# main.net
KiCad netlist of a schematic drawn in Altium Designer
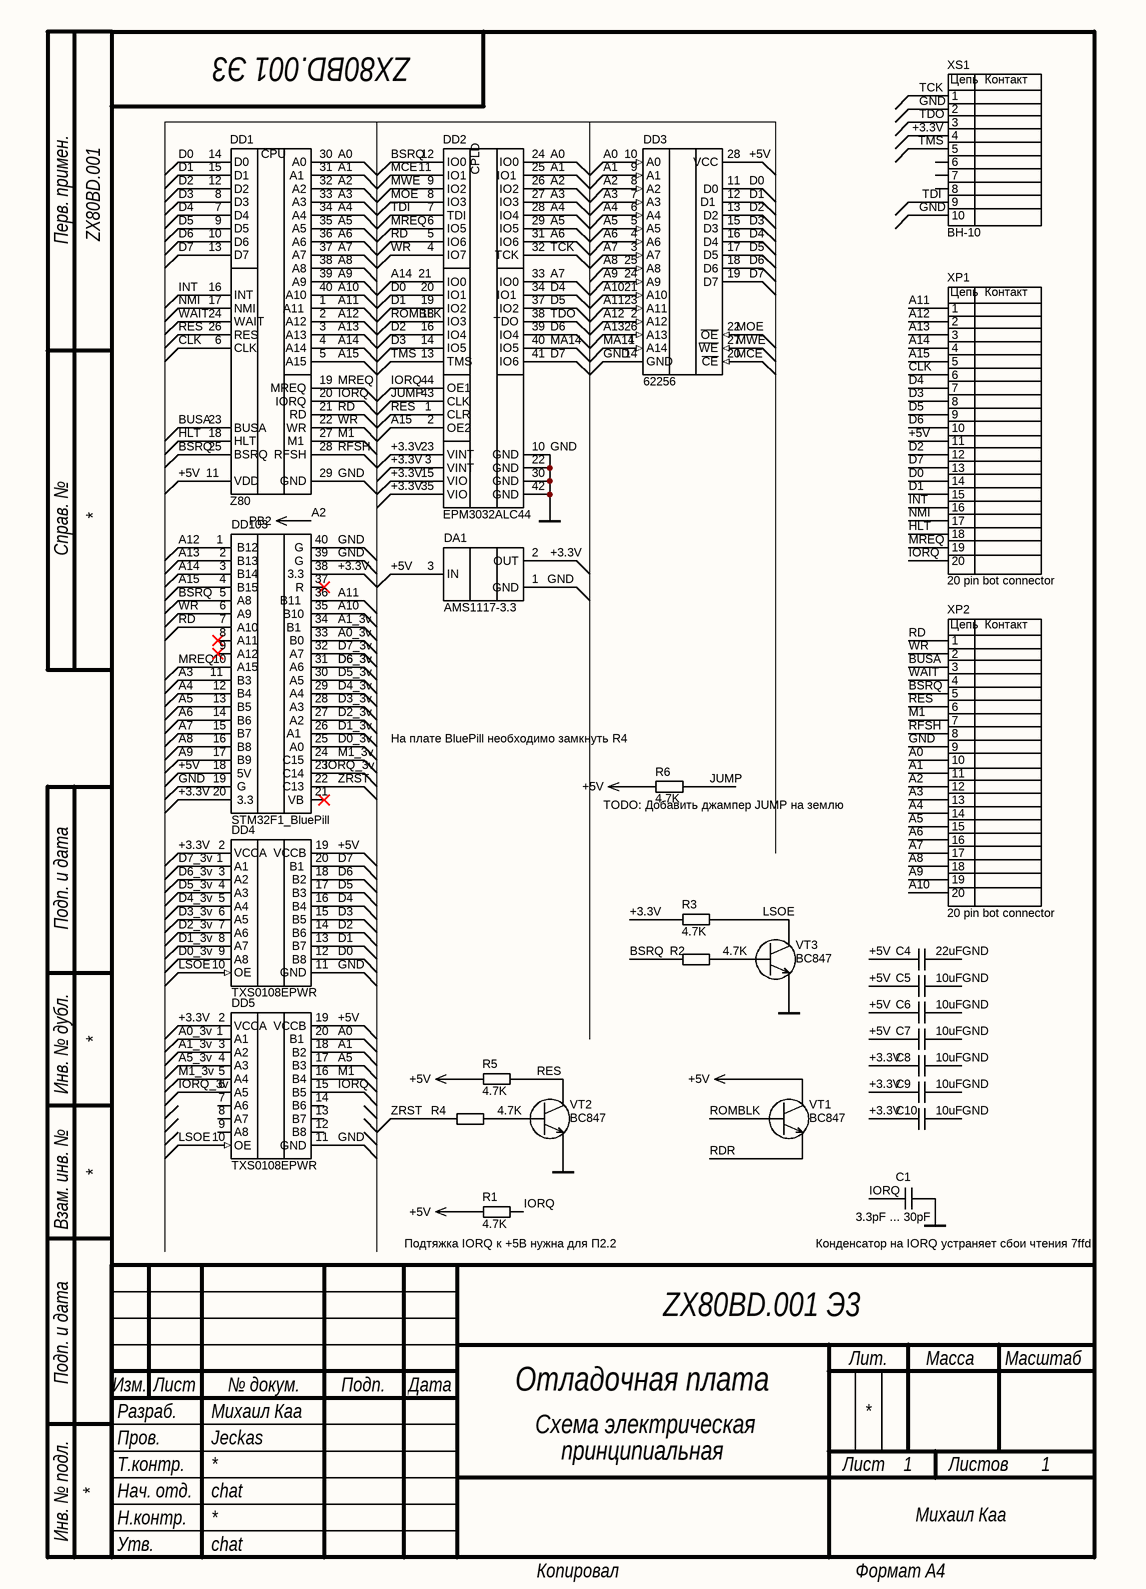
[diagram p0: main.SchDoc]

(export (version "E")
  (design (tool "Eeschema 10.0.6"))
  (components
    (comp (ref "C1")
      (value "3.3pF ... 30pF")
      (footprint "C0805")
      (libsource (lib "Capacitors") (part "CapCer"))
    )
    (comp (ref "C4") (value "22uF") (footprint "С1206") (libsource (lib "Capacitors") (part "CapCer")))
    (comp (ref "C5") (value "10uF") (footprint "C0805") (libsource (lib "Capacitors") (part "CapCer")))
    (comp (ref "C6") (value "10uF") (footprint "C0805") (libsource (lib "Capacitors") (part "CapCer")))
    (comp (ref "C7") (value "10uF") (footprint "C0805") (libsource (lib "Capacitors") (part "CapCer")))
    (comp (ref "C8") (value "10uF") (footprint "C0805") (libsource (lib "Capacitors") (part "CapCer")))
    (comp (ref "C9") (value "10uF") (footprint "C0805") (libsource (lib "Capacitors") (part "CapCer")))
    (comp (ref "C10") (value "10uF") (footprint "C0805") (libsource (lib "Capacitors") (part "CapCer")))
    (comp (ref "DA1")
      (value "AMS1117-3.3")
      (footprint "SOT229P700X180-4N")
      (libsource (lib "LDO") (part "AMS1117-3.3"))
    )
    (comp (ref "DD1")
      (value "Z80")
      (footprint "DIP1540W47P254L5320H635Q40B")
      (libsource (lib "Z80") (part "Z80"))
    )
    (comp (ref "DD2")
      (value "EPM3032ALC44")
      (footprint "PLCC-44-R")
      (description "44-Pin PLCC44")
      (libsource (lib "cpld") (part "EPM3032ALC44"))
    )
    (comp (ref "DD3")
      (value "62256")
      (footprint "DIP28")
      (fields (field (name "MF") "BRADY"))
      (libsource (lib "RAM") (part "62256"))
    )
    (comp (ref "DD4")
      (value "TXS0108EPWR")
      (footprint "SOP65P640X120-20N")
      (description "8-bit bidirectional voltage-level shifter for open-drain and push-pull application")
      (fields (field (name "MF") "Texas Instruments"))
      (libsource (lib "Shifter") (part "TXS0108EPWR"))
    )
    (comp (ref "DD5")
      (value "TXS0108EPWR")
      (footprint "SOP65P640X120-20N")
      (description "8-bit bidirectional voltage-level shifter for open-drain and push-pull application")
      (fields (field (name "MF") "Texas Instruments"))
      (libsource (lib "Shifter") (part "TXS0108EPWR"))
    )
    (comp (ref "DD103")
      (value "STM32F1_BluePill")
      (footprint "PCB-STM32F103")
      (description "STM32F103C8T6")
      (libsource (lib "MCU") (part "STM32F1_BluePill"))
    )
    (comp (ref "R1") (value "4.7K") (footprint "R0805") (libsource (lib "Resistors") (part "Res")))
    (comp (ref "R2") (value "4.7K") (footprint "R0805") (libsource (lib "Resistors") (part "Res")))
    (comp (ref "R3") (value "4.7K") (footprint "R0805") (libsource (lib "Resistors") (part "Res")))
    (comp (ref "R4") (value "4.7K") (footprint "R0805") (libsource (lib "Resistors") (part "Res")))
    (comp (ref "R5") (value "4.7K") (footprint "R0805") (libsource (lib "Resistors") (part "Res")))
    (comp (ref "R6") (value "4.7K") (footprint "R0805") (libsource (lib "Resistors") (part "Res")))
    (comp (ref "VT1")
      (value "BC847")
      (footprint "BC847")
      (description "NPN Transistor")
      (libsource (lib "Transistors") (part "BC847"))
    )
    (comp (ref "VT2")
      (value "BC847")
      (footprint "BC847")
      (description "NPN Transistor")
      (libsource (lib "Transistors") (part "BC847"))
    )
    (comp (ref "VT3")
      (value "BC847")
      (footprint "BC847")
      (description "NPN Transistor")
      (libsource (lib "Transistors") (part "BC847"))
    )
    (comp (ref "XP1")
      (value "20 pin bot connector")
      (footprint "20pin header")
      (description "20 Pin 2.54 mm")
      (libsource (lib "Connectors") (part "20 pin bot connector"))
    )
    (comp (ref "XP2")
      (value "20 pin bot connector")
      (footprint "20pin header")
      (description "20 Pin 2.54 mm")
      (libsource (lib "Connectors") (part "20 pin bot connector"))
    )
    (comp (ref "XS1")
      (value "BH-10")
      (footprint "BH-10")
      (description "10 Position Total Dual Row 2.54 mm Pitch Straight Male Shrouded Box Header")
      (fields (field (name "MF") "Sullins Connector") (field (name "MP") "SBH11-PBPC-D05-ST-BK"))
      (libsource (lib "Connectors") (part "BH-10"))
    )
  )
  (nets
    (net (code "1") (name "+5V") (class "Default")
      (node (ref "C4") (pin "1") (pinfunction "1_1") (pintype "passive"))
      (node (ref "C5") (pin "1") (pinfunction "1_1") (pintype "passive"))
      (node (ref "C6") (pin "1") (pinfunction "1_1") (pintype "passive"))
      (node (ref "C7") (pin "1") (pinfunction "1_1") (pintype "passive"))
      (node (ref "DA1") (pin "3") (pinfunction "IN_3") (pintype "passive"))
      (node (ref "DD1") (pin "11") (pinfunction "VDD_11") (pintype "passive"))
      (node (ref "DD103") (pin "18") (pinfunction "5V_18") (pintype "passive"))
      (node (ref "DD3") (pin "28") (pinfunction "VCC_28") (pintype "power_in"))
      (node (ref "DD4") (pin "19") (pinfunction "VCCB_19") (pintype "power_in"))
      (node (ref "DD5") (pin "19") (pinfunction "VCCB_19") (pintype "power_in"))
      (node (ref "R1") (pin "2") (pinfunction "2_2") (pintype "passive"))
      (node (ref "R5") (pin "2") (pinfunction "2_2") (pintype "passive"))
      (node (ref "R6") (pin "2") (pinfunction "2_2") (pintype "passive"))
      (node (ref "VT1") (pin "3") (pinfunction "C_3") (pintype "power_in"))
      (node (ref "XP1") (pin "11") (pinfunction "11_11") (pintype "passive"))
    )
    (net (code "2") (name "/+3.3V") (class "Default")
      (node (ref "C10") (pin "1") (pinfunction "1_1") (pintype "passive"))
      (node (ref "C8") (pin "1") (pinfunction "1_1") (pintype "passive"))
      (node (ref "C9") (pin "1") (pinfunction "1_1") (pintype "passive"))
      (node (ref "DA1") (pin "2") (pinfunction "OUT_2") (pintype "passive"))
      (node (ref "DD103") (pin "20") (pinfunction "3.3_20") (pintype "passive"))
      (node (ref "DD103") (pin "38") (pinfunction "3.3_38") (pintype "passive"))
      (node (ref "DD2") (pin "15") (pinfunction "VIO_15") (pintype "passive"))
      (node (ref "DD2") (pin "23") (pinfunction "VINT_23") (pintype "passive"))
      (node (ref "DD2") (pin "3") (pinfunction "VINT_3") (pintype "passive"))
      (node (ref "DD2") (pin "35") (pinfunction "VIO_35") (pintype "passive"))
      (node (ref "DD4") (pin "2") (pinfunction "VCCA_2") (pintype "power_in"))
      (node (ref "DD5") (pin "2") (pinfunction "VCCA_2") (pintype "power_in"))
      (node (ref "R3") (pin "2") (pinfunction "2_2") (pintype "passive"))
      (node (ref "XS1") (pin "4") (pinfunction "4_4") (pintype "passive"))
    )
    (net (code "3") (name "/A0") (class "Default")
      (node (ref "DD1") (pin "30") (pinfunction "A0_30") (pintype "passive"))
      (node (ref "DD2") (pin "24") (pinfunction "IO0_24") (pintype "passive"))
      (node (ref "DD3") (pin "10") (pinfunction "A0_10") (pintype "input"))
      (node (ref "DD5") (pin "20") (pinfunction "B1_20") (pintype "bidirectional"))
      (node (ref "XP2") (pin "10") (pinfunction "10_10") (pintype "passive"))
    )
    (net (code "4") (name "/A0_3v") (class "Default")
      (node (ref "DD103") (pin "33") (pinfunction "B0_33") (pintype "passive"))
      (node (ref "DD5") (pin "1") (pinfunction "A1_1") (pintype "bidirectional"))
    )
    (net (code "5") (name "/A1") (class "Default")
      (node (ref "DD1") (pin "31") (pinfunction "A1_31") (pintype "passive"))
      (node (ref "DD2") (pin "25") (pinfunction "IO1_25") (pintype "passive"))
      (node (ref "DD3") (pin "9") (pinfunction "A1_9") (pintype "input"))
      (node (ref "DD5") (pin "18") (pinfunction "B2_18") (pintype "bidirectional"))
      (node (ref "XP2") (pin "11") (pinfunction "11_11") (pintype "passive"))
    )
    (net (code "6") (name "/A1_3v") (class "Default")
      (node (ref "DD103") (pin "34") (pinfunction "B1_34") (pintype "passive"))
      (node (ref "DD5") (pin "3") (pinfunction "A2_3") (pintype "bidirectional"))
    )
    (net (code "7") (name "/A3") (class "Default")
      (node (ref "DD1") (pin "33") (pinfunction "A3_33") (pintype "passive"))
      (node (ref "DD103") (pin "11") (pinfunction "B3_11") (pintype "passive"))
      (node (ref "DD2") (pin "27") (pinfunction "IO3_27") (pintype "passive"))
      (node (ref "DD3") (pin "7") (pinfunction "A3_7") (pintype "input"))
      (node (ref "XP2") (pin "13") (pinfunction "13_13") (pintype "passive"))
    )
    (net (code "8") (name "/A4") (class "Default")
      (node (ref "DD1") (pin "34") (pinfunction "A4_34") (pintype "passive"))
      (node (ref "DD103") (pin "12") (pinfunction "B4_12") (pintype "passive"))
      (node (ref "DD2") (pin "28") (pinfunction "IO4_28") (pintype "passive"))
      (node (ref "DD3") (pin "6") (pinfunction "A4_6") (pintype "input"))
      (node (ref "XP2") (pin "14") (pinfunction "14_14") (pintype "passive"))
    )
    (net (code "9") (name "/A5") (class "Default")
      (node (ref "DD1") (pin "35") (pinfunction "A5_35") (pintype "passive"))
      (node (ref "DD103") (pin "13") (pinfunction "B5_13") (pintype "passive"))
      (node (ref "DD2") (pin "29") (pinfunction "IO5_29") (pintype "passive"))
      (node (ref "DD3") (pin "5") (pinfunction "A5_5") (pintype "input"))
      (node (ref "DD5") (pin "17") (pinfunction "B3_17") (pintype "bidirectional"))
      (node (ref "XP2") (pin "15") (pinfunction "15_15") (pintype "passive"))
    )
    (net (code "10") (name "/A5_3v") (class "Default")
      (node (ref "DD5") (pin "4") (pinfunction "A3_4") (pintype "bidirectional"))
    )
    (net (code "11") (name "/A6") (class "Default")
      (node (ref "DD1") (pin "36") (pinfunction "A6_36") (pintype "passive"))
      (node (ref "DD103") (pin "14") (pinfunction "B6_14") (pintype "passive"))
      (node (ref "DD2") (pin "31") (pinfunction "IO6_31") (pintype "passive"))
      (node (ref "DD3") (pin "4") (pinfunction "A6_4") (pintype "input"))
      (node (ref "XP2") (pin "16") (pinfunction "16_16") (pintype "passive"))
    )
    (net (code "12") (name "/A7") (class "Default")
      (node (ref "DD1") (pin "37") (pinfunction "A7_37") (pintype "passive"))
      (node (ref "DD103") (pin "15") (pinfunction "B7_15") (pintype "passive"))
      (node (ref "DD2") (pin "33") (pinfunction "IO0_33") (pintype "passive"))
      (node (ref "DD3") (pin "3") (pinfunction "A7_3") (pintype "input"))
      (node (ref "XP2") (pin "17") (pinfunction "17_17") (pintype "passive"))
    )
    (net (code "13") (name "/A8") (class "Default")
      (node (ref "DD1") (pin "38") (pinfunction "A8_38") (pintype "passive"))
      (node (ref "DD103") (pin "16") (pinfunction "B8_16") (pintype "passive"))
      (node (ref "DD3") (pin "25") (pinfunction "A8_25") (pintype "input"))
      (node (ref "XP2") (pin "18") (pinfunction "18_18") (pintype "passive"))
    )
    (net (code "14") (name "/A9") (class "Default")
      (node (ref "DD1") (pin "39") (pinfunction "A9_39") (pintype "passive"))
      (node (ref "DD103") (pin "17") (pinfunction "B9_17") (pintype "passive"))
      (node (ref "DD3") (pin "24") (pinfunction "A9_24") (pintype "input"))
      (node (ref "XP2") (pin "19") (pinfunction "19_19") (pintype "passive"))
    )
    (net (code "15") (name "/A10") (class "Default")
      (node (ref "DD1") (pin "40") (pinfunction "A10_40") (pintype "passive"))
      (node (ref "DD103") (pin "35") (pinfunction "B10_35") (pintype "passive"))
      (node (ref "DD3") (pin "21") (pinfunction "A10_21") (pintype "input"))
      (node (ref "XP2") (pin "20") (pinfunction "20_20") (pintype "passive"))
    )
    (net (code "16") (name "/A11") (class "Default")
      (node (ref "DD1") (pin "1") (pinfunction "A11_1") (pintype "passive"))
      (node (ref "DD103") (pin "36") (pinfunction "B11_36") (pintype "passive"))
      (node (ref "DD3") (pin "23") (pinfunction "A11_23") (pintype "input"))
      (node (ref "XP1") (pin "1") (pinfunction "1_1") (pintype "passive"))
    )
    (net (code "17") (name "/A12") (class "Default")
      (node (ref "DD1") (pin "2") (pinfunction "A12_2") (pintype "passive"))
      (node (ref "DD103") (pin "1") (pinfunction "B12_1") (pintype "passive"))
      (node (ref "DD3") (pin "2") (pinfunction "A12_2") (pintype "input"))
      (node (ref "XP1") (pin "2") (pinfunction "2_2") (pintype "passive"))
    )
    (net (code "18") (name "/A13") (class "Default")
      (node (ref "DD1") (pin "3") (pinfunction "A13_3") (pintype "passive"))
      (node (ref "DD103") (pin "2") (pinfunction "B13_2") (pintype "passive"))
      (node (ref "DD3") (pin "26") (pinfunction "A13_26") (pintype "input"))
      (node (ref "XP1") (pin "3") (pinfunction "3_3") (pintype "passive"))
    )
    (net (code "19") (name "/A14") (class "Default")
      (node (ref "DD1") (pin "4") (pinfunction "A14_4") (pintype "passive"))
      (node (ref "DD103") (pin "3") (pinfunction "B14_3") (pintype "passive"))
      (node (ref "DD2") (pin "21") (pinfunction "IO0_21") (pintype "passive"))
      (node (ref "XP1") (pin "4") (pinfunction "4_4") (pintype "passive"))
    )
    (net (code "20") (name "/A15") (class "Default")
      (node (ref "DD1") (pin "5") (pinfunction "A15_5") (pintype "passive"))
      (node (ref "DD103") (pin "4") (pinfunction "B15_4") (pintype "passive"))
      (node (ref "DD2") (pin "2") (pinfunction "OE2_2") (pintype "passive"))
      (node (ref "XP1") (pin "5") (pinfunction "5_5") (pintype "passive"))
    )
    (net (code "21") (name "/BSRQ") (class "Default")
      (node (ref "DD1") (pin "25") (pinfunction "BSRQ_25") (pintype "passive"))
      (node (ref "DD103") (pin "5") (pinfunction "A8_5") (pintype "passive"))
      (node (ref "DD2") (pin "12") (pinfunction "IO0_12") (pintype "passive"))
      (node (ref "R2") (pin "1") (pinfunction "1_1") (pintype "passive"))
      (node (ref "XP2") (pin "5") (pinfunction "5_5") (pintype "passive"))
    )
    (net (code "22") (name "/BUSA") (class "Default")
      (node (ref "DD1") (pin "23") (pinfunction "BUSA_23") (pintype "passive"))
      (node (ref "XP2") (pin "3") (pinfunction "3_3") (pintype "passive"))
    )
    (net (code "23") (name "/CLK") (class "Default")
      (node (ref "DD1") (pin "6") (pinfunction "CLK_6") (pintype "passive"))
      (node (ref "XP1") (pin "6") (pinfunction "6_6") (pintype "passive"))
    )
    (net (code "24") (name "/D0") (class "Default")
      (node (ref "DD1") (pin "14") (pinfunction "D0_14") (pintype "passive"))
      (node (ref "DD2") (pin "20") (pinfunction "IO1_20") (pintype "passive"))
      (node (ref "DD3") (pin "11") (pinfunction "D0_11") (pintype "bidirectional"))
      (node (ref "DD4") (pin "12") (pinfunction "B8_12") (pintype "bidirectional"))
      (node (ref "XP1") (pin "14") (pinfunction "14_14") (pintype "passive"))
    )
    (net (code "25") (name "/D0_3v") (class "Default")
      (node (ref "DD103") (pin "25") (pinfunction "A0_25") (pintype "passive"))
      (node (ref "DD4") (pin "9") (pinfunction "A8_9") (pintype "bidirectional"))
    )
    (net (code "26") (name "/D1") (class "Default")
      (node (ref "DD1") (pin "15") (pinfunction "D1_15") (pintype "passive"))
      (node (ref "DD2") (pin "19") (pinfunction "IO2_19") (pintype "passive"))
      (node (ref "DD3") (pin "12") (pinfunction "D1_12") (pintype "bidirectional"))
      (node (ref "DD4") (pin "13") (pinfunction "B7_13") (pintype "bidirectional"))
      (node (ref "XP1") (pin "15") (pinfunction "15_15") (pintype "passive"))
    )
    (net (code "27") (name "/D1_3v") (class "Default")
      (node (ref "DD103") (pin "26") (pinfunction "A1_26") (pintype "passive"))
      (node (ref "DD4") (pin "8") (pinfunction "A7_8") (pintype "bidirectional"))
    )
    (net (code "28") (name "/D2") (class "Default")
      (node (ref "DD1") (pin "12") (pinfunction "D2_12") (pintype "passive"))
      (node (ref "DD2") (pin "16") (pinfunction "IO4_16") (pintype "passive"))
      (node (ref "DD3") (pin "13") (pinfunction "D2_13") (pintype "bidirectional"))
      (node (ref "DD4") (pin "14") (pinfunction "B6_14") (pintype "bidirectional"))
      (node (ref "XP1") (pin "12") (pinfunction "12_12") (pintype "passive"))
    )
    (net (code "29") (name "/D2_3v") (class "Default")
      (node (ref "DD103") (pin "27") (pinfunction "A2_27") (pintype "passive"))
      (node (ref "DD4") (pin "7") (pinfunction "A6_7") (pintype "bidirectional"))
    )
    (net (code "30") (name "/D3") (class "Default")
      (node (ref "DD1") (pin "8") (pinfunction "D3_8") (pintype "passive"))
      (node (ref "DD2") (pin "14") (pinfunction "IO5_14") (pintype "passive"))
      (node (ref "DD3") (pin "15") (pinfunction "D3_15") (pintype "bidirectional"))
      (node (ref "DD4") (pin "15") (pinfunction "B5_15") (pintype "bidirectional"))
      (node (ref "XP1") (pin "8") (pinfunction "8_8") (pintype "passive"))
    )
    (net (code "31") (name "/D3_3v") (class "Default")
      (node (ref "DD103") (pin "28") (pinfunction "A3_28") (pintype "passive"))
      (node (ref "DD4") (pin "6") (pinfunction "A5_6") (pintype "bidirectional"))
    )
    (net (code "32") (name "/D4") (class "Default")
      (node (ref "DD1") (pin "7") (pinfunction "D4_7") (pintype "passive"))
      (node (ref "DD2") (pin "34") (pinfunction "IO1_34") (pintype "passive"))
      (node (ref "DD3") (pin "16") (pinfunction "D4_16") (pintype "bidirectional"))
      (node (ref "DD4") (pin "16") (pinfunction "B4_16") (pintype "bidirectional"))
      (node (ref "XP1") (pin "7") (pinfunction "7_7") (pintype "passive"))
    )
    (net (code "33") (name "/D4_3v") (class "Default")
      (node (ref "DD103") (pin "29") (pinfunction "A4_29") (pintype "passive"))
      (node (ref "DD4") (pin "5") (pinfunction "A4_5") (pintype "bidirectional"))
    )
    (net (code "34") (name "/D5") (class "Default")
      (node (ref "DD1") (pin "9") (pinfunction "D5_9") (pintype "passive"))
      (node (ref "DD2") (pin "37") (pinfunction "IO2_37") (pintype "passive"))
      (node (ref "DD3") (pin "17") (pinfunction "D5_17") (pintype "bidirectional"))
      (node (ref "DD4") (pin "17") (pinfunction "B3_17") (pintype "bidirectional"))
      (node (ref "XP1") (pin "9") (pinfunction "9_9") (pintype "passive"))
    )
    (net (code "35") (name "/D5_3v") (class "Default")
      (node (ref "DD103") (pin "30") (pinfunction "A5_30") (pintype "passive"))
      (node (ref "DD4") (pin "4") (pinfunction "A3_4") (pintype "bidirectional"))
    )
    (net (code "36") (name "/D6") (class "Default")
      (node (ref "DD1") (pin "10") (pinfunction "D6_10") (pintype "passive"))
      (node (ref "DD2") (pin "39") (pinfunction "IO4_39") (pintype "passive"))
      (node (ref "DD3") (pin "18") (pinfunction "D6_18") (pintype "bidirectional"))
      (node (ref "DD4") (pin "18") (pinfunction "B2_18") (pintype "bidirectional"))
      (node (ref "XP1") (pin "10") (pinfunction "10_10") (pintype "passive"))
    )
    (net (code "37") (name "/D6_3v") (class "Default")
      (node (ref "DD103") (pin "31") (pinfunction "A6_31") (pintype "passive"))
      (node (ref "DD4") (pin "3") (pinfunction "A2_3") (pintype "bidirectional"))
    )
    (net (code "38") (name "/D7") (class "Default")
      (node (ref "DD1") (pin "13") (pinfunction "D7_13") (pintype "passive"))
      (node (ref "DD2") (pin "41") (pinfunction "IO6_41") (pintype "passive"))
      (node (ref "DD3") (pin "19") (pinfunction "D7_19") (pintype "bidirectional"))
      (node (ref "DD4") (pin "20") (pinfunction "B1_20") (pintype "bidirectional"))
      (node (ref "XP1") (pin "13") (pinfunction "13_13") (pintype "passive"))
    )
    (net (code "39") (name "/D7_3v") (class "Default")
      (node (ref "DD103") (pin "32") (pinfunction "A7_32") (pintype "passive"))
      (node (ref "DD4") (pin "1") (pinfunction "A1_1") (pintype "bidirectional"))
    )
    (net (code "40") (name "/HLT") (class "Default")
      (node (ref "DD1") (pin "18") (pinfunction "HLT_18") (pintype "passive"))
      (node (ref "XP1") (pin "18") (pinfunction "18_18") (pintype "passive"))
    )
    (net (code "41") (name "/INT") (class "Default")
      (node (ref "DD1") (pin "16") (pinfunction "INT_16") (pintype "passive"))
      (node (ref "XP1") (pin "16") (pinfunction "16_16") (pintype "passive"))
    )
    (net (code "42") (name "/IORQ") (class "Default")
      (node (ref "C1") (pin "1") (pinfunction "1_1") (pintype "passive"))
      (node (ref "DD1") (pin "20") (pinfunction "IORQ_20") (pintype "passive"))
      (node (ref "DD2") (pin "44") (pinfunction "OE1_44") (pintype "passive"))
      (node (ref "DD5") (pin "15") (pinfunction "B5_15") (pintype "bidirectional"))
      (node (ref "R1") (pin "1") (pinfunction "1_1") (pintype "passive"))
      (node (ref "XP1") (pin "20") (pinfunction "20_20") (pintype "passive"))
    )
    (net (code "43") (name "/IORQ_3v") (class "Default")
      (node (ref "DD103") (pin "23") (pinfunction "C14_23") (pintype "passive"))
      (node (ref "DD5") (pin "6") (pinfunction "A5_6") (pintype "bidirectional"))
    )
    (net (code "44") (name "/JUMP") (class "Default")
      (node (ref "DD2") (pin "43") (pinfunction "CLK_43") (pintype "passive"))
      (node (ref "R6") (pin "1") (pinfunction "1_1") (pintype "passive"))
    )
    (net (code "45") (name "/LSOE") (class "Default")
      (node (ref "DD4") (pin "10") (pinfunction "OE_10") (pintype "input"))
      (node (ref "DD5") (pin "10") (pinfunction "OE_10") (pintype "input"))
      (node (ref "R3") (pin "1") (pinfunction "1_1") (pintype "passive"))
      (node (ref "VT3") (pin "3") (pinfunction "C_3") (pintype "power_in"))
    )
    (net (code "46") (name "/M1") (class "Default")
      (node (ref "DD1") (pin "27") (pinfunction "M1_27") (pintype "passive"))
      (node (ref "DD5") (pin "16") (pinfunction "B4_16") (pintype "bidirectional"))
      (node (ref "XP2") (pin "7") (pinfunction "7_7") (pintype "passive"))
    )
    (net (code "47") (name "/M1_3v") (class "Default")
      (node (ref "DD103") (pin "24") (pinfunction "C15_24") (pintype "passive"))
      (node (ref "DD5") (pin "5") (pinfunction "A4_5") (pintype "bidirectional"))
    )
    (net (code "48") (name "/MA14") (class "Default")
      (node (ref "DD2") (pin "40") (pinfunction "IO5_40") (pintype "passive"))
      (node (ref "DD3") (pin "1") (pinfunction "A14_1") (pintype "input"))
    )
    (net (code "49") (name "/MCE") (class "Default")
      (node (ref "DD2") (pin "11") (pinfunction "IO1_11") (pintype "passive"))
      (node (ref "DD3") (pin "20") (pinfunction "~{CE}_20") (pintype "input"))
    )
    (net (code "50") (name "/MOE") (class "Default")
      (node (ref "DD2") (pin "8") (pinfunction "IO3_8") (pintype "passive"))
      (node (ref "DD3") (pin "22") (pinfunction "~{OE}_22") (pintype "input"))
    )
    (net (code "51") (name "/MREQ") (class "Default")
      (node (ref "DD1") (pin "19") (pinfunction "MREQ_19") (pintype "passive"))
      (node (ref "DD103") (pin "10") (pinfunction "A15_10") (pintype "passive"))
      (node (ref "DD2") (pin "6") (pinfunction "IO5_6") (pintype "passive"))
      (node (ref "XP1") (pin "19") (pinfunction "19_19") (pintype "passive"))
    )
    (net (code "52") (name "/MWE") (class "Default")
      (node (ref "DD2") (pin "9") (pinfunction "IO2_9") (pintype "passive"))
      (node (ref "DD3") (pin "27") (pinfunction "~{WE}_27") (pintype "input"))
    )
    (net (code "53") (name "/NMI") (class "Default")
      (node (ref "DD1") (pin "17") (pinfunction "NMI_17") (pintype "passive"))
      (node (ref "XP1") (pin "17") (pinfunction "17_17") (pintype "passive"))
    )
    (net (code "54") (name "/RD") (class "Default")
      (node (ref "DD1") (pin "21") (pinfunction "RD_21") (pintype "passive"))
      (node (ref "DD103") (pin "7") (pinfunction "A10_7") (pintype "passive"))
      (node (ref "DD2") (pin "5") (pinfunction "IO6_5") (pintype "passive"))
      (node (ref "XP2") (pin "1") (pinfunction "1_1") (pintype "passive"))
    )
    (net (code "55") (name "/RDR") (class "Default")
      (node (ref "VT1") (pin "2") (pinfunction "E_2") (pintype "power_in"))
    )
    (net (code "56") (name "/RES") (class "Default")
      (node (ref "DD1") (pin "26") (pinfunction "RES_26") (pintype "passive"))
      (node (ref "DD2") (pin "1") (pinfunction "CLR_1") (pintype "passive"))
      (node (ref "R5") (pin "1") (pinfunction "1_1") (pintype "passive"))
      (node (ref "VT2") (pin "3") (pinfunction "C_3") (pintype "power_in"))
      (node (ref "XP2") (pin "6") (pinfunction "6_6") (pintype "passive"))
    )
    (net (code "57") (name "/RFSH") (class "Default")
      (node (ref "DD1") (pin "28") (pinfunction "RFSH_28") (pintype "passive"))
      (node (ref "XP2") (pin "8") (pinfunction "8_8") (pintype "passive"))
    )
    (net (code "58") (name "/ROMBLK") (class "Default")
      (node (ref "DD2") (pin "18") (pinfunction "IO3_18") (pintype "passive"))
      (node (ref "VT1") (pin "1") (pinfunction "B_1") (pintype "power_in"))
    )
    (net (code "59") (name "/TCK") (class "Default")
      (node (ref "DD2") (pin "32") (pinfunction "TCK_32") (pintype "passive"))
      (node (ref "XS1") (pin "1") (pinfunction "1_1") (pintype "passive"))
    )
    (net (code "60") (name "/TDI") (class "Default")
      (node (ref "DD2") (pin "7") (pinfunction "TDI_7") (pintype "passive"))
      (node (ref "XS1") (pin "9") (pinfunction "9_9") (pintype "passive"))
    )
    (net (code "61") (name "/TDO") (class "Default")
      (node (ref "DD2") (pin "38") (pinfunction "TDO_38") (pintype "passive"))
      (node (ref "XS1") (pin "3") (pinfunction "3_3") (pintype "passive"))
    )
    (net (code "62") (name "/TMS") (class "Default")
      (node (ref "DD2") (pin "13") (pinfunction "TMS_13") (pintype "passive"))
      (node (ref "XS1") (pin "5") (pinfunction "5_5") (pintype "passive"))
    )
    (net (code "63") (name "/WAIT") (class "Default")
      (node (ref "DD1") (pin "24") (pinfunction "WAIT_24") (pintype "passive"))
      (node (ref "XP2") (pin "4") (pinfunction "4_4") (pintype "passive"))
    )
    (net (code "64") (name "/WR") (class "Default")
      (node (ref "DD1") (pin "22") (pinfunction "WR_22") (pintype "passive"))
      (node (ref "DD103") (pin "6") (pinfunction "A9_6") (pintype "passive"))
      (node (ref "DD2") (pin "4") (pinfunction "IO7_4") (pintype "passive"))
      (node (ref "XP2") (pin "2") (pinfunction "2_2") (pintype "passive"))
    )
    (net (code "65") (name "/ZRST") (class "Default")
      (node (ref "DD103") (pin "22") (pinfunction "C13_22") (pintype "passive"))
      (node (ref "R4") (pin "1") (pinfunction "1_1") (pintype "passive"))
    )
    (net (code "66") (name "GND") (class "Default")
      (node (ref "C1") (pin "2") (pinfunction "2_2") (pintype "passive"))
      (node (ref "C10") (pin "2") (pinfunction "2_2") (pintype "passive"))
      (node (ref "C4") (pin "2") (pinfunction "2_2") (pintype "passive"))
      (node (ref "C5") (pin "2") (pinfunction "2_2") (pintype "passive"))
      (node (ref "C6") (pin "2") (pinfunction "2_2") (pintype "passive"))
      (node (ref "C7") (pin "2") (pinfunction "2_2") (pintype "passive"))
      (node (ref "C8") (pin "2") (pinfunction "2_2") (pintype "passive"))
      (node (ref "C9") (pin "2") (pinfunction "2_2") (pintype "passive"))
      (node (ref "DA1") (pin "1") (pinfunction "GND_1") (pintype "passive"))
      (node (ref "DD1") (pin "29") (pinfunction "GND_29") (pintype "passive"))
      (node (ref "DD103") (pin "19") (pinfunction "G_19") (pintype "passive"))
      (node (ref "DD103") (pin "39") (pinfunction "G_39") (pintype "passive"))
      (node (ref "DD103") (pin "40") (pinfunction "G_40") (pintype "passive"))
      (node (ref "DD2") (pin "10") (pinfunction "GND_10") (pintype "passive"))
      (node (ref "DD2") (pin "22") (pinfunction "GND_22") (pintype "passive"))
      (node (ref "DD2") (pin "30") (pinfunction "GND_30") (pintype "passive"))
      (node (ref "DD2") (pin "42") (pinfunction "GND_42") (pintype "passive"))
      (node (ref "DD3") (pin "14") (pinfunction "GND_14") (pintype "power_in"))
      (node (ref "DD4") (pin "11") (pinfunction "GND_11") (pintype "power_in"))
      (node (ref "DD5") (pin "11") (pinfunction "GND_11") (pintype "power_in"))
      (node (ref "VT2") (pin "2") (pinfunction "E_2") (pintype "power_in"))
      (node (ref "VT3") (pin "2") (pinfunction "E_2") (pintype "power_in"))
      (node (ref "XP2") (pin "9") (pinfunction "9_9") (pintype "passive"))
      (node (ref "XS1") (pin "10") (pinfunction "10_10") (pintype "passive"))
      (node (ref "XS1") (pin "2") (pinfunction "2_2") (pintype "passive"))
    )
    (net (code "67") (name "Net-(VT2-B)") (class "Default")
      (node (ref "R4") (pin "2") (pinfunction "2_2") (pintype "passive"))
      (node (ref "VT2") (pin "1") (pinfunction "B_1") (pintype "power_in"))
    )
    (net (code "68") (name "Net-(VT3-B)") (class "Default")
      (node (ref "R2") (pin "2") (pinfunction "2_2") (pintype "passive"))
      (node (ref "VT3") (pin "1") (pinfunction "B_1") (pintype "power_in"))
    )
    (net (code "69") (name "PB2") (class "Default")
      (node (ref "DD1") (pin "32") (pinfunction "A2_32") (pintype "passive"))
      (node (ref "DD2") (pin "26") (pinfunction "IO2_26") (pintype "passive"))
      (node (ref "DD3") (pin "8") (pinfunction "A2_8") (pintype "input"))
      (node (ref "XP2") (pin "12") (pinfunction "12_12") (pintype "passive"))
    )
    (net (code "70") (name "unconnected-(DD5-A6-Pad7)") (class "Default")
      (node (ref "DD5") (pin "7") (pinfunction "A6_7") (pintype "bidirectional"))
    )
    (net (code "71") (name "unconnected-(DD5-A7-Pad8)") (class "Default")
      (node (ref "DD5") (pin "8") (pinfunction "A7_8") (pintype "bidirectional"))
    )
    (net (code "72") (name "unconnected-(DD5-A8-Pad9)") (class "Default")
      (node (ref "DD5") (pin "9") (pinfunction "A8_9") (pintype "bidirectional"))
    )
    (net (code "73") (name "unconnected-(DD5-B6-Pad14)") (class "Default")
      (node (ref "DD5") (pin "14") (pinfunction "B6_14") (pintype "bidirectional"))
    )
    (net (code "74") (name "unconnected-(DD5-B7-Pad13)") (class "Default")
      (node (ref "DD5") (pin "13") (pinfunction "B7_13") (pintype "bidirectional"))
    )
    (net (code "75") (name "unconnected-(DD5-B8-Pad12)") (class "Default")
      (node (ref "DD5") (pin "12") (pinfunction "B8_12") (pintype "bidirectional"))
    )
    (net (code "76") (name "unconnected-(DD103-A11-Pad8)") (class "Default")
      (node (ref "DD103") (pin "8") (pinfunction "A11_8") (pintype "passive+no_connect"))
    )
    (net (code "77") (name "unconnected-(DD103-A12-Pad9)") (class "Default")
      (node (ref "DD103") (pin "9") (pinfunction "A12_9") (pintype "passive+no_connect"))
    )
    (net (code "78") (name "unconnected-(DD103-R-Pad37)") (class "Default")
      (node (ref "DD103") (pin "37") (pinfunction "R_37") (pintype "passive+no_connect"))
    )
    (net (code "79") (name "unconnected-(DD103-VB-Pad21)") (class "Default")
      (node (ref "DD103") (pin "21") (pinfunction "VB_21") (pintype "passive+no_connect"))
    )
    (net (code "80") (name "unconnected-(XS1-Pad6)") (class "Default")
      (node (ref "XS1") (pin "6") (pinfunction "6_6") (pintype "passive"))
    )
    (net (code "81") (name "unconnected-(XS1-Pad7)") (class "Default")
      (node (ref "XS1") (pin "7") (pinfunction "7_7") (pintype "passive"))
    )
    (net (code "82") (name "unconnected-(XS1-Pad8)") (class "Default")
      (node (ref "XS1") (pin "8") (pinfunction "8_8") (pintype "passive"))
    )
  )
)
